# IrrigationSystemShield.net
KiCad netlist of a schematic drawn in EAGLE
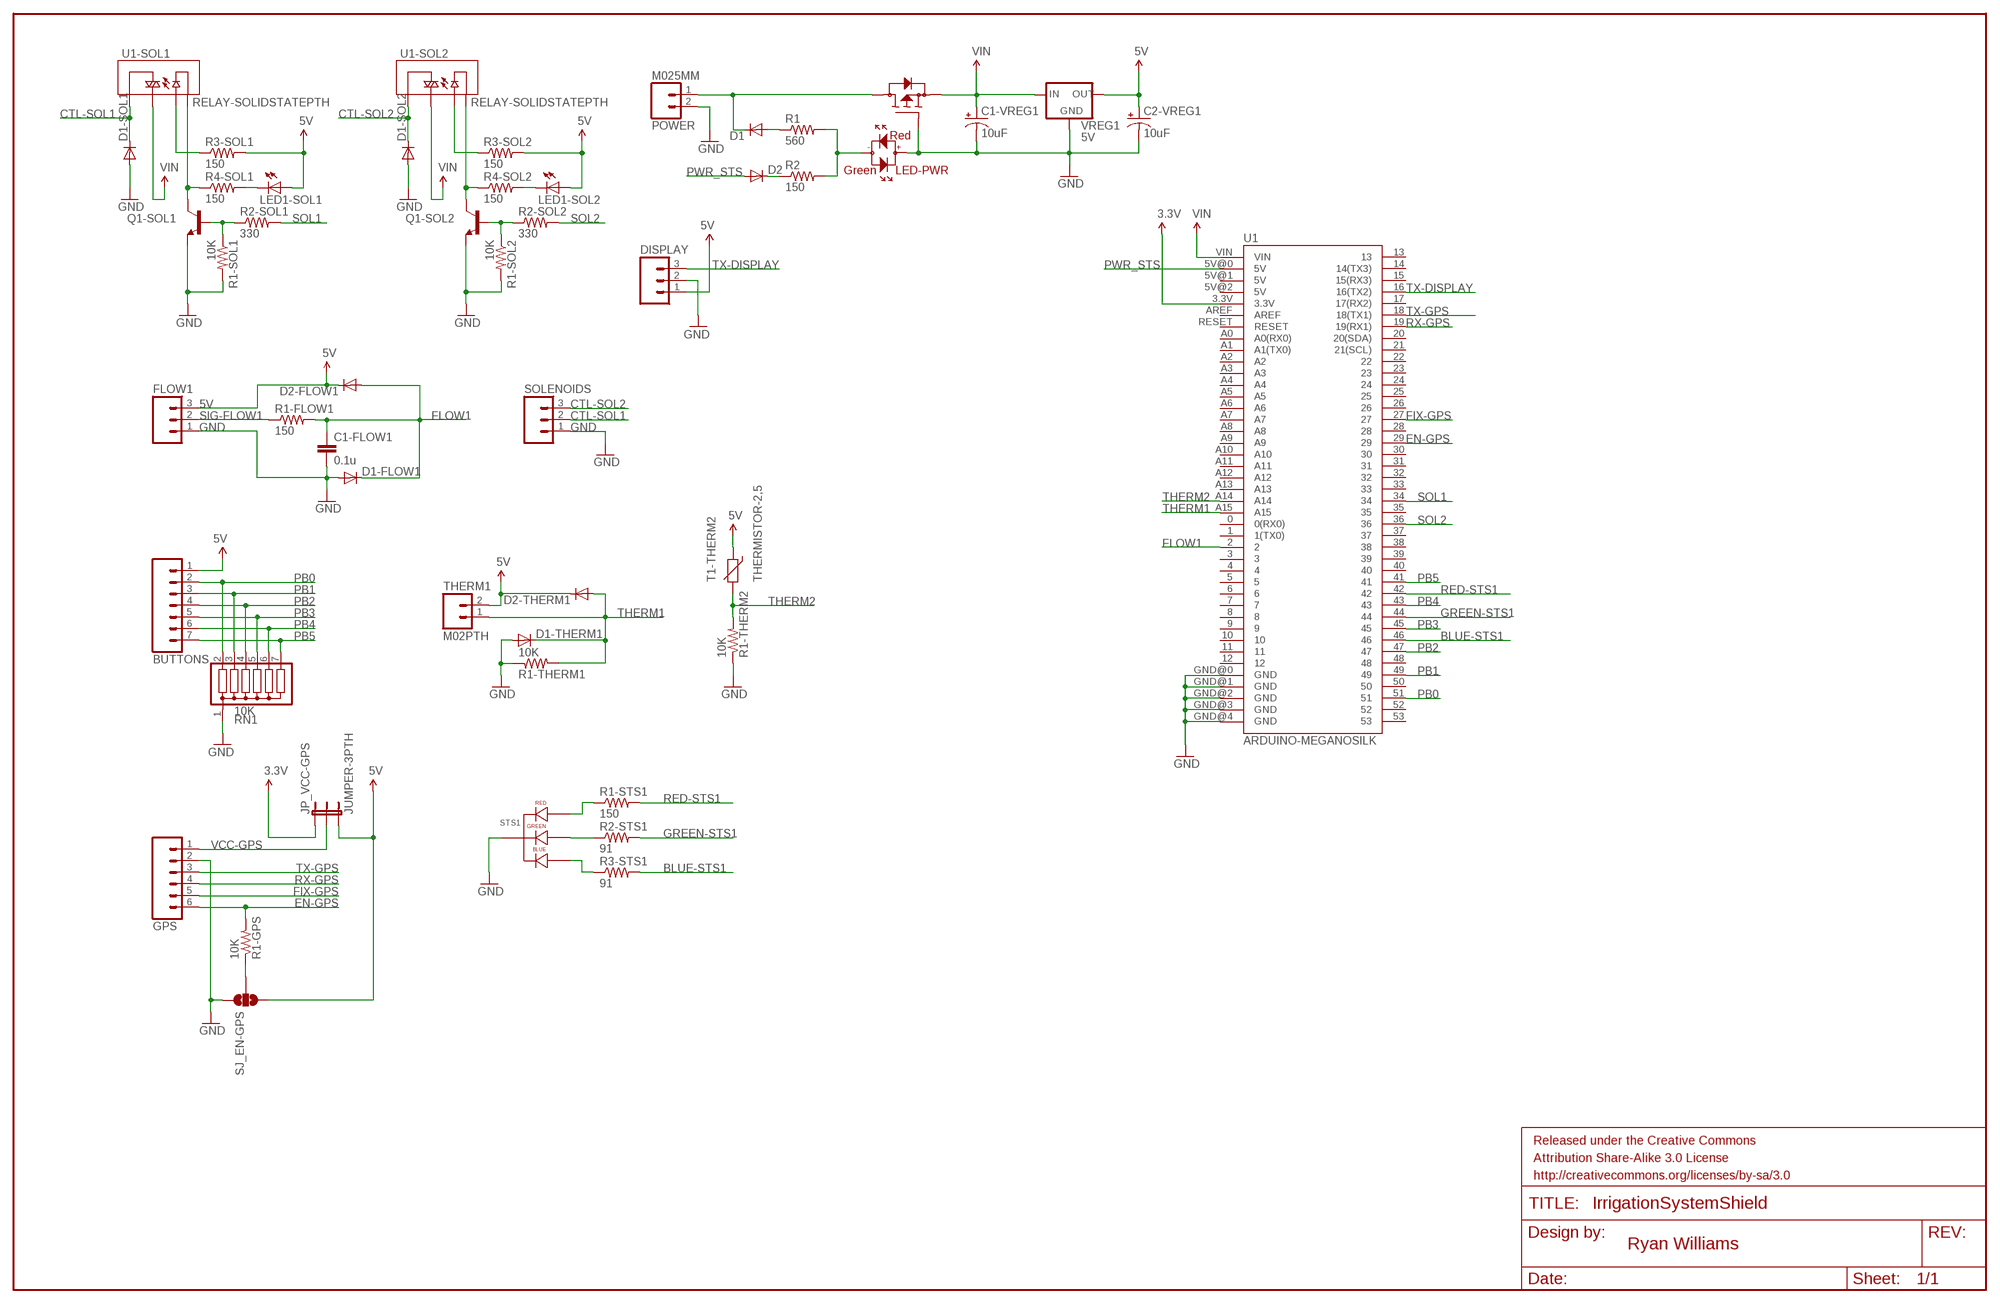
[diagram p0: schematic, sheet 1]

(export (version "E")
  (design (tool "Eeschema 10.0.6"))
  (components
    (comp (ref "BUTTONS")
      (value "M07")
      (footprint "eagle-import:1X07")
      (libsource (lib "eagle-import") (part "M07"))
    )
    (comp (ref "C1-FLOW1")
      (value "0.1u")
      (footprint "eagle-import:CAP-PTH-5MM")
      (libsource (lib "eagle-import") (part "CAPPTH1"))
    )
    (comp (ref "C1-VREG1")
      (value "10uF")
      (footprint "eagle-import:CPOL-RADIAL-10UF-25V")
      (libsource (lib "eagle-import") (part "10UF-25V-20%(PTH)"))
    )
    (comp (ref "C2-VREG1")
      (value "10uF")
      (footprint "eagle-import:CPOL-RADIAL-10UF-25V")
      (libsource (lib "eagle-import") (part "10UF-25V-20%(PTH)"))
    )
    (comp (ref "D1")
      (value "DIODEPTH")
      (footprint "eagle-import:DIODE-1N4001")
      (libsource (lib "eagle-import") (part "DIODEPTH"))
    )
    (comp (ref "D1-FLOW1")
      (value "DIODE1N4148")
      (footprint "eagle-import:DIODE-1N4148")
      (libsource (lib "eagle-import") (part "DIODE1N4148"))
    )
    (comp (ref "D1-SOL1")
      (value "DIODEPTH")
      (footprint "eagle-import:DIODE-1N4001")
      (libsource (lib "eagle-import") (part "DIODEPTH"))
    )
    (comp (ref "D1-SOL2")
      (value "DIODEPTH")
      (footprint "eagle-import:DIODE-1N4001")
      (libsource (lib "eagle-import") (part "DIODEPTH"))
    )
    (comp (ref "D1-THERM1")
      (value "DIODE1N4148")
      (footprint "eagle-import:DIODE-1N4148")
      (libsource (lib "eagle-import") (part "DIODE1N4148"))
    )
    (comp (ref "D2")
      (value "DIODEPTH")
      (footprint "eagle-import:DIODE-1N4001")
      (libsource (lib "eagle-import") (part "DIODEPTH"))
    )
    (comp (ref "D2-FLOW1")
      (value "DIODE1N4148")
      (footprint "eagle-import:DIODE-1N4148")
      (libsource (lib "eagle-import") (part "DIODE1N4148"))
    )
    (comp (ref "D2-THERM1")
      (value "DIODE1N4148")
      (footprint "eagle-import:DIODE-1N4148")
      (libsource (lib "eagle-import") (part "DIODE1N4148"))
    )
    (comp (ref "DISPLAY")
      (value "M03JST-PTH")
      (footprint "eagle-import:JST-3-PTH")
      (libsource (lib "eagle-import") (part "M03JST-PTH"))
    )
    (comp (ref "FET-1")
      (value "P-FET")
      (footprint "eagle-import:FQP27P06")
      (libsource (lib "eagle-import") (part "P-FET"))
    )
    (comp (ref "FLOW1")
      (value "M03-SCREW-5MM")
      (footprint "eagle-import:SCREWTERMINAL-5MM-3")
      (libsource (lib "eagle-import") (part "M03-SCREW-5MM"))
    )
    (comp (ref "FRAME1")
      (value "FRAME-LEDGER")
      (footprint "eagle-import:CREATIVE_COMMONS")
      (libsource (lib "eagle-import") (part "FRAME-LEDGER"))
    )
    (comp (ref "GPS")
      (value "M06SIP")
      (footprint "eagle-import:1X06")
      (libsource (lib "eagle-import") (part "M06SIP"))
    )
    (comp (ref "JP_VCC-GPS")
      (value "JUMPER-3PTH")
      (footprint "eagle-import:1X03")
      (libsource (lib "eagle-import") (part "JUMPER-3PTH"))
    )
    (comp (ref "LED-PWR")
      (value "LED-BIPOLARHGL*3362")
      (footprint "eagle-import:LED-5MM")
      (libsource (lib "eagle-import") (part "LED-BIPOLARL3362HG"))
    )
    (comp (ref "LED1-SOL1")
      (value "LED5MM")
      (footprint "eagle-import:LED5MM")
      (libsource (lib "eagle-import") (part "LED5MM"))
    )
    (comp (ref "LED1-SOL2")
      (value "LED5MM")
      (footprint "eagle-import:LED5MM")
      (libsource (lib "eagle-import") (part "LED5MM"))
    )
    (comp (ref "POWER")
      (value "M025MM")
      (footprint "eagle-import:SCREWTERMINAL-5MM-2")
      (libsource (lib "eagle-import") (part "M025MM"))
    )
    (comp (ref "Q1-SOL1")
      (value "TRANSISTOR_NPNTO92")
      (footprint "eagle-import:TO-92")
      (libsource (lib "eagle-import") (part "TRANSISTOR_NPNTO92"))
    )
    (comp (ref "Q1-SOL2")
      (value "TRANSISTOR_NPNTO92")
      (footprint "eagle-import:TO-92")
      (libsource (lib "eagle-import") (part "TRANSISTOR_NPNTO92"))
    )
    (comp (ref "R1")
      (value "560")
      (footprint "eagle-import:AXIAL-0.5")
      (libsource (lib "eagle-import") (part "RESISTORPTH-1/2W"))
    )
    (comp (ref "R1-FLOW1")
      (value "150")
      (footprint "eagle-import:AXIAL-0.4")
      (libsource (lib "eagle-import") (part "RESISTORPTH-1/4W"))
    )
    (comp (ref "R1-GPS")
      (value "10K")
      (footprint "eagle-import:AXIAL-0.4")
      (libsource (lib "eagle-import") (part "RESISTORPTH-1/4W"))
    )
    (comp (ref "R1-SOL1")
      (value "10K")
      (footprint "eagle-import:AXIAL-0.4")
      (libsource (lib "eagle-import") (part "RESISTORPTH-1/4W"))
    )
    (comp (ref "R1-SOL2")
      (value "10K")
      (footprint "eagle-import:AXIAL-0.4")
      (libsource (lib "eagle-import") (part "RESISTORPTH-1/4W"))
    )
    (comp (ref "R1-STS1")
      (value "150")
      (footprint "eagle-import:AXIAL-0.4")
      (libsource (lib "eagle-import") (part "RESISTORPTH-1/4W"))
    )
    (comp (ref "R1-THERM1")
      (value "10K")
      (footprint "eagle-import:AXIAL-0.4")
      (libsource (lib "eagle-import") (part "RESISTORPTH-1/4W"))
    )
    (comp (ref "R1-THERM2")
      (value "10K")
      (footprint "eagle-import:AXIAL-0.4")
      (libsource (lib "eagle-import") (part "RESISTORPTH-1/4W"))
    )
    (comp (ref "R2")
      (value "150")
      (footprint "eagle-import:AXIAL-0.4")
      (libsource (lib "eagle-import") (part "RESISTORPTH-1/4W"))
    )
    (comp (ref "R2-SOL1")
      (value "330")
      (footprint "eagle-import:AXIAL-0.4")
      (libsource (lib "eagle-import") (part "RESISTORPTH-1/4W"))
    )
    (comp (ref "R2-SOL2")
      (value "330")
      (footprint "eagle-import:AXIAL-0.4")
      (libsource (lib "eagle-import") (part "RESISTORPTH-1/4W"))
    )
    (comp (ref "R2-STS1")
      (value "91")
      (footprint "eagle-import:AXIAL-0.4")
      (libsource (lib "eagle-import") (part "RESISTORPTH-1/4W"))
    )
    (comp (ref "R3-SOL1")
      (value "150")
      (footprint "eagle-import:AXIAL-0.4")
      (libsource (lib "eagle-import") (part "RESISTORPTH-1/4W"))
    )
    (comp (ref "R3-SOL2")
      (value "150")
      (footprint "eagle-import:AXIAL-0.4")
      (libsource (lib "eagle-import") (part "RESISTORPTH-1/4W"))
    )
    (comp (ref "R3-STS1")
      (value "91")
      (footprint "eagle-import:AXIAL-0.4")
      (libsource (lib "eagle-import") (part "RESISTORPTH-1/4W"))
    )
    (comp (ref "R4-SOL1")
      (value "150")
      (footprint "eagle-import:AXIAL-0.4")
      (libsource (lib "eagle-import") (part "RESISTORPTH-1/4W"))
    )
    (comp (ref "R4-SOL2")
      (value "150")
      (footprint "eagle-import:AXIAL-0.4")
      (libsource (lib "eagle-import") (part "RESISTORPTH-1/4W"))
    )
    (comp (ref "RN1")
      (value "10K")
      (footprint "eagle-import:SIL7")
      (libsource (lib "eagle-import") (part "G06R"))
    )
    (comp (ref "SJ_EN-GPS")
      (value "SOLDERJUMPER_2WAYS")
      (footprint "eagle-import:SJ_3")
      (libsource (lib "eagle-import") (part "SOLDERJUMPER_2WAYS"))
    )
    (comp (ref "SOLENOIDS")
      (value "M03-SCREW-5MM")
      (footprint "eagle-import:SCREWTERMINAL-5MM-3")
      (libsource (lib "eagle-import") (part "M03-SCREW-5MM"))
    )
    (comp (ref "STS1")
      (value "LED-RGB-CC-THRUDIFFUSE")
      (footprint "eagle-import:LED-RGB-THRU")
      (libsource (lib "eagle-import") (part "LED-RGB-CC-THRUDIFFUSE"))
    )
    (comp (ref "T1-THERM2")
      (value "THERMISTOR-2,5")
      (footprint "eagle-import:RS-2,5")
      (libsource (lib "eagle-import") (part "THERMISTOR-2,5"))
    )
    (comp (ref "THERM1")
      (value "M02PTH")
      (footprint "eagle-import:1X02")
      (libsource (lib "eagle-import") (part "M02PTH"))
    )
    (comp (ref "U1")
      (value "ARDUINO-MEGANOSILK")
      (footprint "eagle-import:ARDUINO_MEGA_NOSILK")
      (libsource (lib "eagle-import") (part "ARDUINO-MEGANOSILK"))
    )
    (comp (ref "U1-SOL1")
      (value "RELAY-SOLIDSTATEPTH")
      (footprint "eagle-import:RELAY-S108T02")
      (libsource (lib "eagle-import") (part "RELAY-SOLIDSTATEPTH"))
    )
    (comp (ref "U1-SOL2")
      (value "RELAY-SOLIDSTATEPTH")
      (footprint "eagle-import:RELAY-S108T02")
      (libsource (lib "eagle-import") (part "RELAY-SOLIDSTATEPTH"))
    )
    (comp (ref "VREG1")
      (value "5V")
      (footprint "eagle-import:TO220-IGO")
      (libsource (lib "eagle-import") (part "V_REG_78XXSINK"))
    )
  )
  (nets
    (net (code "1") (name "/BLUE-STS1") (class "Default")
      (node (ref "R3-STS1") (pin "P$2") (pinfunction "2_P$2") (pintype "passive"))
      (node (ref "U1") (pin "46") (pinfunction "46_46") (pintype "bidirectional"))
    )
    (net (code "2") (name "/CTL-SOL1") (class "Default")
      (node (ref "D1-SOL1") (pin "C") (pinfunction "C_C") (pintype "passive"))
      (node (ref "SOLENOIDS") (pin "2") (pinfunction "2_2") (pintype "passive"))
      (node (ref "U1-SOL1") (pin "1") (pinfunction "T1_1") (pintype "bidirectional"))
    )
    (net (code "3") (name "/CTL-SOL2") (class "Default")
      (node (ref "D1-SOL2") (pin "C") (pinfunction "C_C") (pintype "passive"))
      (node (ref "SOLENOIDS") (pin "3") (pinfunction "3_3") (pintype "passive"))
      (node (ref "U1-SOL2") (pin "1") (pinfunction "T1_1") (pintype "bidirectional"))
    )
    (net (code "4") (name "/EN-GPS") (class "Default")
      (node (ref "GPS") (pin "6") (pinfunction "6_6") (pintype "passive"))
      (node (ref "R1-GPS") (pin "P$2") (pinfunction "2_P$2") (pintype "passive"))
      (node (ref "U1") (pin "29") (pinfunction "29_29") (pintype "bidirectional"))
    )
    (net (code "5") (name "/FIX-GPS") (class "Default")
      (node (ref "GPS") (pin "5") (pinfunction "5_5") (pintype "passive"))
      (node (ref "U1") (pin "27") (pinfunction "27_27") (pintype "bidirectional"))
    )
    (net (code "6") (name "/FLOW1") (class "Default")
      (node (ref "C1-FLOW1") (pin "1") (pinfunction "1_1") (pintype "passive"))
      (node (ref "D1-FLOW1") (pin "C") (pinfunction "C_C") (pintype "passive"))
      (node (ref "D2-FLOW1") (pin "A") (pinfunction "A_A") (pintype "passive"))
      (node (ref "R1-FLOW1") (pin "P$2") (pinfunction "2_P$2") (pintype "passive"))
      (node (ref "U1") (pin "2") (pinfunction "2_2") (pintype "bidirectional"))
    )
    (net (code "7") (name "/GREEN-STS1") (class "Default")
      (node (ref "R2-STS1") (pin "P$2") (pinfunction "2_P$2") (pintype "passive"))
      (node (ref "U1") (pin "44") (pinfunction "44_44") (pintype "bidirectional"))
    )
    (net (code "8") (name "/PB0") (class "Default")
      (node (ref "BUTTONS") (pin "2") (pinfunction "2_2") (pintype "passive"))
      (node (ref "RN1") (pin "2") (pinfunction "2_2") (pintype "passive"))
      (node (ref "U1") (pin "51") (pinfunction "51_51") (pintype "bidirectional"))
    )
    (net (code "9") (name "/PB1") (class "Default")
      (node (ref "BUTTONS") (pin "3") (pinfunction "3_3") (pintype "passive"))
      (node (ref "RN1") (pin "3") (pinfunction "3_3") (pintype "passive"))
      (node (ref "U1") (pin "49") (pinfunction "49_49") (pintype "bidirectional"))
    )
    (net (code "10") (name "/PB2") (class "Default")
      (node (ref "BUTTONS") (pin "4") (pinfunction "4_4") (pintype "passive"))
      (node (ref "RN1") (pin "4") (pinfunction "4_4") (pintype "passive"))
      (node (ref "U1") (pin "47") (pinfunction "47_47") (pintype "bidirectional"))
    )
    (net (code "11") (name "/PB3") (class "Default")
      (node (ref "BUTTONS") (pin "5") (pinfunction "5_5") (pintype "passive"))
      (node (ref "RN1") (pin "5") (pinfunction "5_5") (pintype "passive"))
      (node (ref "U1") (pin "45") (pinfunction "45_45") (pintype "bidirectional"))
    )
    (net (code "12") (name "/PB4") (class "Default")
      (node (ref "BUTTONS") (pin "6") (pinfunction "6_6") (pintype "passive"))
      (node (ref "RN1") (pin "6") (pinfunction "6_6") (pintype "passive"))
      (node (ref "U1") (pin "43") (pinfunction "43_43") (pintype "bidirectional"))
    )
    (net (code "13") (name "/PB5") (class "Default")
      (node (ref "BUTTONS") (pin "7") (pinfunction "7_7") (pintype "passive"))
      (node (ref "RN1") (pin "7") (pinfunction "7_7") (pintype "passive"))
      (node (ref "U1") (pin "41") (pinfunction "41_41") (pintype "bidirectional"))
    )
    (net (code "14") (name "/PWR_STS") (class "Default")
      (node (ref "D2") (pin "A") (pinfunction "A_A") (pintype "passive"))
      (node (ref "U1") (pin "5V@0") (pinfunction "5V_5V@0") (pintype "bidirectional"))
    )
    (net (code "15") (name "/RED-STS1") (class "Default")
      (node (ref "R1-STS1") (pin "P$2") (pinfunction "2_P$2") (pintype "passive"))
      (node (ref "U1") (pin "42") (pinfunction "42_42") (pintype "bidirectional"))
    )
    (net (code "16") (name "/RX-GPS") (class "Default")
      (node (ref "GPS") (pin "4") (pinfunction "4_4") (pintype "passive"))
      (node (ref "U1") (pin "19") (pinfunction "19(RX1)_19") (pintype "bidirectional"))
    )
    (net (code "17") (name "/SIG-FLOW1") (class "Default")
      (node (ref "FLOW1") (pin "2") (pinfunction "2_2") (pintype "passive"))
      (node (ref "R1-FLOW1") (pin "P$1") (pinfunction "1_P$1") (pintype "passive"))
    )
    (net (code "18") (name "/SOL1") (class "Default")
      (node (ref "R2-SOL1") (pin "P$2") (pinfunction "2_P$2") (pintype "passive"))
      (node (ref "U1") (pin "34") (pinfunction "34_34") (pintype "bidirectional"))
    )
    (net (code "19") (name "/SOL2") (class "Default")
      (node (ref "R2-SOL2") (pin "P$2") (pinfunction "2_P$2") (pintype "passive"))
      (node (ref "U1") (pin "36") (pinfunction "36_36") (pintype "bidirectional"))
    )
    (net (code "20") (name "/THERM1") (class "Default")
      (node (ref "D1-THERM1") (pin "C") (pinfunction "C_C") (pintype "passive"))
      (node (ref "D2-THERM1") (pin "A") (pinfunction "A_A") (pintype "passive"))
      (node (ref "R1-THERM1") (pin "P$2") (pinfunction "2_P$2") (pintype "passive"))
      (node (ref "THERM1") (pin "1") (pinfunction "1_1") (pintype "passive"))
      (node (ref "U1") (pin "A15") (pinfunction "A15_A15") (pintype "bidirectional"))
    )
    (net (code "21") (name "/THERM2") (class "Default")
      (node (ref "R1-THERM2") (pin "P$2") (pinfunction "2_P$2") (pintype "passive"))
      (node (ref "T1-THERM2") (pin "2") (pinfunction "2_2") (pintype "passive"))
      (node (ref "U1") (pin "A14") (pinfunction "A14_A14") (pintype "bidirectional"))
    )
    (net (code "22") (name "/TX-DISPLAY") (class "Default")
      (node (ref "DISPLAY") (pin "3") (pinfunction "3_3") (pintype "passive"))
      (node (ref "U1") (pin "16") (pinfunction "16(TX2)_16") (pintype "bidirectional"))
    )
    (net (code "23") (name "/TX-GPS") (class "Default")
      (node (ref "GPS") (pin "3") (pinfunction "3_3") (pintype "passive"))
      (node (ref "U1") (pin "18") (pinfunction "18(TX1)_18") (pintype "bidirectional"))
    )
    (net (code "24") (name "/VCC-GPS") (class "Default")
      (node (ref "GPS") (pin "1") (pinfunction "1_1") (pintype "passive"))
      (node (ref "JP_VCC-GPS") (pin "2") (pinfunction "2_2") (pintype "passive"))
    )
    (net (code "25") (name "3.3V") (class "Default")
      (node (ref "JP_VCC-GPS") (pin "1") (pinfunction "1_1") (pintype "passive"))
      (node (ref "U1") (pin "3.3V") (pinfunction "3.3V_3.3V") (pintype "bidirectional"))
    )
    (net (code "26") (name "5V") (class "Default")
      (node (ref "BUTTONS") (pin "1") (pinfunction "1_1") (pintype "passive"))
      (node (ref "C2-VREG1") (pin "1") (pinfunction "+_1") (pintype "passive"))
      (node (ref "D2-FLOW1") (pin "C") (pinfunction "C_C") (pintype "passive"))
      (node (ref "D2-THERM1") (pin "C") (pinfunction "C_C") (pintype "passive"))
      (node (ref "DISPLAY") (pin "1") (pinfunction "1_1") (pintype "passive"))
      (node (ref "FLOW1") (pin "3") (pinfunction "3_3") (pintype "passive"))
      (node (ref "JP_VCC-GPS") (pin "3") (pinfunction "3_3") (pintype "passive"))
      (node (ref "LED1-SOL1") (pin "A") (pinfunction "A_A") (pintype "passive"))
      (node (ref "LED1-SOL2") (pin "A") (pinfunction "A_A") (pintype "passive"))
      (node (ref "R3-SOL1") (pin "P$2") (pinfunction "2_P$2") (pintype "passive"))
      (node (ref "R3-SOL2") (pin "P$2") (pinfunction "2_P$2") (pintype "passive"))
      (node (ref "SJ_EN-GPS") (pin "3") (pinfunction "3_3") (pintype "passive"))
      (node (ref "T1-THERM2") (pin "1") (pinfunction "1_1") (pintype "passive"))
      (node (ref "THERM1") (pin "2") (pinfunction "2_2") (pintype "passive"))
      (node (ref "VREG1") (pin "OUT") (pinfunction "OUT_OUT") (pintype "output"))
    )
    (net (code "27") (name "GND") (class "Default")
      (node (ref "C1-FLOW1") (pin "2") (pinfunction "2_2") (pintype "passive"))
      (node (ref "C1-VREG1") (pin "2") (pinfunction "-_2") (pintype "passive"))
      (node (ref "C2-VREG1") (pin "2") (pinfunction "-_2") (pintype "passive"))
      (node (ref "D1-FLOW1") (pin "A") (pinfunction "A_A") (pintype "passive"))
      (node (ref "D1-SOL1") (pin "A") (pinfunction "A_A") (pintype "passive"))
      (node (ref "D1-SOL2") (pin "A") (pinfunction "A_A") (pintype "passive"))
      (node (ref "D1-THERM1") (pin "A") (pinfunction "A_A") (pintype "passive"))
      (node (ref "DISPLAY") (pin "2") (pinfunction "2_2") (pintype "passive"))
      (node (ref "FET-1") (pin "GATE") (pinfunction "GATE_GATE") (pintype "bidirectional"))
      (node (ref "FLOW1") (pin "1") (pinfunction "1_1") (pintype "passive"))
      (node (ref "GPS") (pin "2") (pinfunction "2_2") (pintype "passive"))
      (node (ref "LED-PWR") (pin "ANODE") (pinfunction "ANODE_ANODE") (pintype "bidirectional"))
      (node (ref "POWER") (pin "2") (pinfunction "2_2") (pintype "passive"))
      (node (ref "Q1-SOL1") (pin "1") (pinfunction "E_1") (pintype "passive"))
      (node (ref "Q1-SOL2") (pin "1") (pinfunction "E_1") (pintype "passive"))
      (node (ref "R1-SOL1") (pin "P$2") (pinfunction "2_P$2") (pintype "passive"))
      (node (ref "R1-SOL2") (pin "P$2") (pinfunction "2_P$2") (pintype "passive"))
      (node (ref "R1-THERM1") (pin "P$1") (pinfunction "1_P$1") (pintype "passive"))
      (node (ref "R1-THERM2") (pin "P$1") (pinfunction "1_P$1") (pintype "passive"))
      (node (ref "RN1") (pin "1") (pinfunction "1_1") (pintype "passive"))
      (node (ref "SJ_EN-GPS") (pin "1") (pinfunction "1_1") (pintype "passive"))
      (node (ref "SOLENOIDS") (pin "1") (pinfunction "1_1") (pintype "passive"))
      (node (ref "STS1") (pin "2") (pinfunction "CATHODE_2") (pintype "bidirectional"))
      (node (ref "U1") (pin "GND@0") (pinfunction "GND_GND@0") (pintype "bidirectional"))
      (node (ref "U1") (pin "GND@1") (pinfunction "GND_GND@1") (pintype "bidirectional"))
      (node (ref "U1") (pin "GND@2") (pinfunction "GND_GND@2") (pintype "bidirectional"))
      (node (ref "U1") (pin "GND@3") (pinfunction "GND_GND@3") (pintype "bidirectional"))
      (node (ref "U1") (pin "GND@4") (pinfunction "GND_GND@4") (pintype "bidirectional"))
      (node (ref "VREG1") (pin "GND") (pinfunction "GND_GND") (pintype "input"))
    )
    (net (code "28") (name "Net-(D1-PadC)") (class "Default")
      (node (ref "D1") (pin "C") (pinfunction "C_C") (pintype "passive"))
      (node (ref "FET-1") (pin "DRAIN") (pinfunction "DRAIN_DRAIN") (pintype "bidirectional"))
      (node (ref "POWER") (pin "1") (pinfunction "1_1") (pintype "passive"))
    )
    (net (code "29") (name "Net-(LED1-SOL1-C)") (class "Default")
      (node (ref "LED1-SOL1") (pin "K") (pinfunction "C_K") (pintype "passive"))
      (node (ref "R4-SOL1") (pin "P$2") (pinfunction "2_P$2") (pintype "passive"))
    )
    (net (code "30") (name "Net-(LED1-SOL2-C)") (class "Default")
      (node (ref "LED1-SOL2") (pin "K") (pinfunction "C_K") (pintype "passive"))
      (node (ref "R4-SOL2") (pin "P$2") (pinfunction "2_P$2") (pintype "passive"))
    )
    (net (code "31") (name "Net-(Q1-SOL1-B)") (class "Default")
      (node (ref "Q1-SOL1") (pin "2") (pinfunction "B_2") (pintype "passive"))
      (node (ref "R1-SOL1") (pin "P$1") (pinfunction "1_P$1") (pintype "passive"))
      (node (ref "R2-SOL1") (pin "P$1") (pinfunction "1_P$1") (pintype "passive"))
    )
    (net (code "32") (name "Net-(Q1-SOL1-C)") (class "Default")
      (node (ref "Q1-SOL1") (pin "3") (pinfunction "C_3") (pintype "passive"))
      (node (ref "R4-SOL1") (pin "P$1") (pinfunction "1_P$1") (pintype "passive"))
      (node (ref "U1-SOL1") (pin "4") (pinfunction "-_4") (pintype "bidirectional"))
    )
    (net (code "33") (name "Net-(Q1-SOL2-B)") (class "Default")
      (node (ref "Q1-SOL2") (pin "2") (pinfunction "B_2") (pintype "passive"))
      (node (ref "R1-SOL2") (pin "P$1") (pinfunction "1_P$1") (pintype "passive"))
      (node (ref "R2-SOL2") (pin "P$1") (pinfunction "1_P$1") (pintype "passive"))
    )
    (net (code "34") (name "Net-(Q1-SOL2-C)") (class "Default")
      (node (ref "Q1-SOL2") (pin "3") (pinfunction "C_3") (pintype "passive"))
      (node (ref "R4-SOL2") (pin "P$1") (pinfunction "1_P$1") (pintype "passive"))
      (node (ref "U1-SOL2") (pin "4") (pinfunction "-_4") (pintype "bidirectional"))
    )
    (net (code "35") (name "Net-(R1-1)") (class "Default")
      (node (ref "D1") (pin "A") (pinfunction "A_A") (pintype "passive"))
      (node (ref "R1") (pin "P$1") (pinfunction "1_P$1") (pintype "passive"))
    )
    (net (code "36") (name "Net-(R1-2)") (class "Default")
      (node (ref "LED-PWR") (pin "CATHODE") (pinfunction "CATHODE_CATHODE") (pintype "bidirectional"))
      (node (ref "R1") (pin "P$2") (pinfunction "2_P$2") (pintype "passive"))
      (node (ref "R2") (pin "P$2") (pinfunction "2_P$2") (pintype "passive"))
    )
    (net (code "37") (name "Net-(R1-GPS-1)") (class "Default")
      (node (ref "R1-GPS") (pin "P$1") (pinfunction "1_P$1") (pintype "passive"))
      (node (ref "SJ_EN-GPS") (pin "2") (pinfunction "2_2") (pintype "passive"))
    )
    (net (code "38") (name "Net-(R1-STS1-1)") (class "Default")
      (node (ref "R1-STS1") (pin "P$1") (pinfunction "1_P$1") (pintype "passive"))
      (node (ref "STS1") (pin "1") (pinfunction "RED_CATHODE_1") (pintype "bidirectional"))
    )
    (net (code "39") (name "Net-(R2-1)") (class "Default")
      (node (ref "D2") (pin "C") (pinfunction "C_C") (pintype "passive"))
      (node (ref "R2") (pin "P$1") (pinfunction "1_P$1") (pintype "passive"))
    )
    (net (code "40") (name "Net-(R2-STS1-1)") (class "Default")
      (node (ref "R2-STS1") (pin "P$1") (pinfunction "1_P$1") (pintype "passive"))
      (node (ref "STS1") (pin "3") (pinfunction "GREEN_CATHODE_3") (pintype "bidirectional"))
    )
    (net (code "41") (name "Net-(R3-SOL1-1)") (class "Default")
      (node (ref "R3-SOL1") (pin "P$1") (pinfunction "1_P$1") (pintype "passive"))
      (node (ref "U1-SOL1") (pin "3") (pinfunction "+_3") (pintype "bidirectional"))
    )
    (net (code "42") (name "Net-(R3-SOL2-1)") (class "Default")
      (node (ref "R3-SOL2") (pin "P$1") (pinfunction "1_P$1") (pintype "passive"))
      (node (ref "U1-SOL2") (pin "3") (pinfunction "+_3") (pintype "bidirectional"))
    )
    (net (code "43") (name "Net-(R3-STS1-1)") (class "Default")
      (node (ref "R3-STS1") (pin "P$1") (pinfunction "1_P$1") (pintype "passive"))
      (node (ref "STS1") (pin "4") (pinfunction "BLUE_CATHODE_4") (pintype "bidirectional"))
    )
    (net (code "44") (name "VIN") (class "Default")
      (node (ref "C1-VREG1") (pin "1") (pinfunction "+_1") (pintype "passive"))
      (node (ref "FET-1") (pin "SOURCE") (pinfunction "SOURCE_SOURCE") (pintype "bidirectional"))
      (node (ref "U1") (pin "VIN") (pinfunction "VIN_VIN") (pintype "bidirectional"))
      (node (ref "U1-SOL1") (pin "2") (pinfunction "T2_2") (pintype "bidirectional"))
      (node (ref "U1-SOL2") (pin "2") (pinfunction "T2_2") (pintype "bidirectional"))
      (node (ref "VREG1") (pin "IN") (pinfunction "IN_IN") (pintype "input"))
    )
    (net (code "45") (name "unconnected-(U1-0(RX0)-Pad0)") (class "Default")
      (node (ref "U1") (pin "0") (pinfunction "0(RX0)_0") (pintype "bidirectional"))
    )
    (net (code "46") (name "unconnected-(U1-1(TX0)-Pad1)") (class "Default")
      (node (ref "U1") (pin "1") (pinfunction "1(TX0)_1") (pintype "bidirectional"))
    )
    (net (code "47") (name "unconnected-(U1-5V-Pad5V@1)") (class "Default")
      (node (ref "U1") (pin "5V@1") (pinfunction "5V_5V@1") (pintype "bidirectional"))
    )
    (net (code "48") (name "unconnected-(U1-5V-Pad5V@2)") (class "Default")
      (node (ref "U1") (pin "5V@2") (pinfunction "5V_5V@2") (pintype "bidirectional"))
    )
    (net (code "49") (name "unconnected-(U1-14(TX3)-Pad14)") (class "Default")
      (node (ref "U1") (pin "14") (pinfunction "14(TX3)_14") (pintype "bidirectional"))
    )
    (net (code "50") (name "unconnected-(U1-15(RX3)-Pad15)") (class "Default")
      (node (ref "U1") (pin "15") (pinfunction "15(RX3)_15") (pintype "bidirectional"))
    )
    (net (code "51") (name "unconnected-(U1-17(RX2)-Pad17)") (class "Default")
      (node (ref "U1") (pin "17") (pinfunction "17(RX2)_17") (pintype "bidirectional"))
    )
    (net (code "52") (name "unconnected-(U1-20(SDA)-Pad20)") (class "Default")
      (node (ref "U1") (pin "20") (pinfunction "20(SDA)_20") (pintype "bidirectional"))
    )
    (net (code "53") (name "unconnected-(U1-21(SCL)-Pad21)") (class "Default")
      (node (ref "U1") (pin "21") (pinfunction "21(SCL)_21") (pintype "bidirectional"))
    )
    (net (code "54") (name "unconnected-(U1-A0(RX0)-PadA0)") (class "Default")
      (node (ref "U1") (pin "A0") (pinfunction "A0(RX0)_A0") (pintype "bidirectional"))
    )
    (net (code "55") (name "unconnected-(U1-A1(TX0)-PadA1)") (class "Default")
      (node (ref "U1") (pin "A1") (pinfunction "A1(TX0)_A1") (pintype "bidirectional"))
    )
    (net (code "56") (name "unconnected-(U1-Pad3)") (class "Default")
      (node (ref "U1") (pin "3") (pinfunction "3_3") (pintype "bidirectional"))
    )
    (net (code "57") (name "unconnected-(U1-Pad4)") (class "Default")
      (node (ref "U1") (pin "4") (pinfunction "4_4") (pintype "bidirectional"))
    )
    (net (code "58") (name "unconnected-(U1-Pad5)") (class "Default")
      (node (ref "U1") (pin "5") (pinfunction "5_5") (pintype "bidirectional"))
    )
    (net (code "59") (name "unconnected-(U1-Pad6)") (class "Default")
      (node (ref "U1") (pin "6") (pinfunction "6_6") (pintype "bidirectional"))
    )
    (net (code "60") (name "unconnected-(U1-Pad7)") (class "Default")
      (node (ref "U1") (pin "7") (pinfunction "7_7") (pintype "bidirectional"))
    )
    (net (code "61") (name "unconnected-(U1-Pad8)") (class "Default")
      (node (ref "U1") (pin "8") (pinfunction "8_8") (pintype "bidirectional"))
    )
    (net (code "62") (name "unconnected-(U1-Pad9)") (class "Default")
      (node (ref "U1") (pin "9") (pinfunction "9_9") (pintype "bidirectional"))
    )
    (net (code "63") (name "unconnected-(U1-Pad10)") (class "Default")
      (node (ref "U1") (pin "10") (pinfunction "10_10") (pintype "bidirectional"))
    )
    (net (code "64") (name "unconnected-(U1-Pad11)") (class "Default")
      (node (ref "U1") (pin "11") (pinfunction "11_11") (pintype "bidirectional"))
    )
    (net (code "65") (name "unconnected-(U1-Pad12)") (class "Default")
      (node (ref "U1") (pin "12") (pinfunction "12_12") (pintype "bidirectional"))
    )
    (net (code "66") (name "unconnected-(U1-Pad13)") (class "Default")
      (node (ref "U1") (pin "13") (pinfunction "13_13") (pintype "bidirectional"))
    )
    (net (code "67") (name "unconnected-(U1-Pad22)") (class "Default")
      (node (ref "U1") (pin "22") (pinfunction "22_22") (pintype "bidirectional"))
    )
    (net (code "68") (name "unconnected-(U1-Pad23)") (class "Default")
      (node (ref "U1") (pin "23") (pinfunction "23_23") (pintype "bidirectional"))
    )
    (net (code "69") (name "unconnected-(U1-Pad24)") (class "Default")
      (node (ref "U1") (pin "24") (pinfunction "24_24") (pintype "bidirectional"))
    )
    (net (code "70") (name "unconnected-(U1-Pad25)") (class "Default")
      (node (ref "U1") (pin "25") (pinfunction "25_25") (pintype "bidirectional"))
    )
    (net (code "71") (name "unconnected-(U1-Pad26)") (class "Default")
      (node (ref "U1") (pin "26") (pinfunction "26_26") (pintype "bidirectional"))
    )
    (net (code "72") (name "unconnected-(U1-Pad28)") (class "Default")
      (node (ref "U1") (pin "28") (pinfunction "28_28") (pintype "bidirectional"))
    )
    (net (code "73") (name "unconnected-(U1-Pad30)") (class "Default")
      (node (ref "U1") (pin "30") (pinfunction "30_30") (pintype "bidirectional"))
    )
    (net (code "74") (name "unconnected-(U1-Pad31)") (class "Default")
      (node (ref "U1") (pin "31") (pinfunction "31_31") (pintype "bidirectional"))
    )
    (net (code "75") (name "unconnected-(U1-Pad32)") (class "Default")
      (node (ref "U1") (pin "32") (pinfunction "32_32") (pintype "bidirectional"))
    )
    (net (code "76") (name "unconnected-(U1-Pad33)") (class "Default")
      (node (ref "U1") (pin "33") (pinfunction "33_33") (pintype "bidirectional"))
    )
    (net (code "77") (name "unconnected-(U1-Pad35)") (class "Default")
      (node (ref "U1") (pin "35") (pinfunction "35_35") (pintype "bidirectional"))
    )
    (net (code "78") (name "unconnected-(U1-Pad37)") (class "Default")
      (node (ref "U1") (pin "37") (pinfunction "37_37") (pintype "bidirectional"))
    )
    (net (code "79") (name "unconnected-(U1-Pad38)") (class "Default")
      (node (ref "U1") (pin "38") (pinfunction "38_38") (pintype "bidirectional"))
    )
    (net (code "80") (name "unconnected-(U1-Pad39)") (class "Default")
      (node (ref "U1") (pin "39") (pinfunction "39_39") (pintype "bidirectional"))
    )
    (net (code "81") (name "unconnected-(U1-Pad40)") (class "Default")
      (node (ref "U1") (pin "40") (pinfunction "40_40") (pintype "bidirectional"))
    )
    (net (code "82") (name "unconnected-(U1-Pad48)") (class "Default")
      (node (ref "U1") (pin "48") (pinfunction "48_48") (pintype "bidirectional"))
    )
    (net (code "83") (name "unconnected-(U1-Pad50)") (class "Default")
      (node (ref "U1") (pin "50") (pinfunction "50_50") (pintype "bidirectional"))
    )
    (net (code "84") (name "unconnected-(U1-Pad52)") (class "Default")
      (node (ref "U1") (pin "52") (pinfunction "52_52") (pintype "bidirectional"))
    )
    (net (code "85") (name "unconnected-(U1-Pad53)") (class "Default")
      (node (ref "U1") (pin "53") (pinfunction "53_53") (pintype "bidirectional"))
    )
    (net (code "86") (name "unconnected-(U1-PadA2)") (class "Default")
      (node (ref "U1") (pin "A2") (pinfunction "A2_A2") (pintype "bidirectional"))
    )
    (net (code "87") (name "unconnected-(U1-PadA3)") (class "Default")
      (node (ref "U1") (pin "A3") (pinfunction "A3_A3") (pintype "bidirectional"))
    )
    (net (code "88") (name "unconnected-(U1-PadA4)") (class "Default")
      (node (ref "U1") (pin "A4") (pinfunction "A4_A4") (pintype "bidirectional"))
    )
    (net (code "89") (name "unconnected-(U1-PadA5)") (class "Default")
      (node (ref "U1") (pin "A5") (pinfunction "A5_A5") (pintype "bidirectional"))
    )
    (net (code "90") (name "unconnected-(U1-PadA6)") (class "Default")
      (node (ref "U1") (pin "A6") (pinfunction "A6_A6") (pintype "bidirectional"))
    )
    (net (code "91") (name "unconnected-(U1-PadA7)") (class "Default")
      (node (ref "U1") (pin "A7") (pinfunction "A7_A7") (pintype "bidirectional"))
    )
    (net (code "92") (name "unconnected-(U1-PadA8)") (class "Default")
      (node (ref "U1") (pin "A8") (pinfunction "A8_A8") (pintype "bidirectional"))
    )
    (net (code "93") (name "unconnected-(U1-PadA9)") (class "Default")
      (node (ref "U1") (pin "A9") (pinfunction "A9_A9") (pintype "bidirectional"))
    )
    (net (code "94") (name "unconnected-(U1-PadA10)") (class "Default")
      (node (ref "U1") (pin "A10") (pinfunction "A10_A10") (pintype "bidirectional"))
    )
    (net (code "95") (name "unconnected-(U1-PadA11)") (class "Default")
      (node (ref "U1") (pin "A11") (pinfunction "A11_A11") (pintype "bidirectional"))
    )
    (net (code "96") (name "unconnected-(U1-PadA12)") (class "Default")
      (node (ref "U1") (pin "A12") (pinfunction "A12_A12") (pintype "bidirectional"))
    )
    (net (code "97") (name "unconnected-(U1-PadA13)") (class "Default")
      (node (ref "U1") (pin "A13") (pinfunction "A13_A13") (pintype "bidirectional"))
    )
    (net (code "98") (name "unconnected-(U1-PadAREF)") (class "Default")
      (node (ref "U1") (pin "AREF") (pinfunction "AREF_AREF") (pintype "bidirectional"))
    )
    (net (code "99") (name "unconnected-(U1-PadRESET)") (class "Default")
      (node (ref "U1") (pin "RESET") (pinfunction "RESET_RESET") (pintype "bidirectional"))
    )
  )
)
